# GTR.net
KiCad netlist of a schematic drawn in Altium Designer
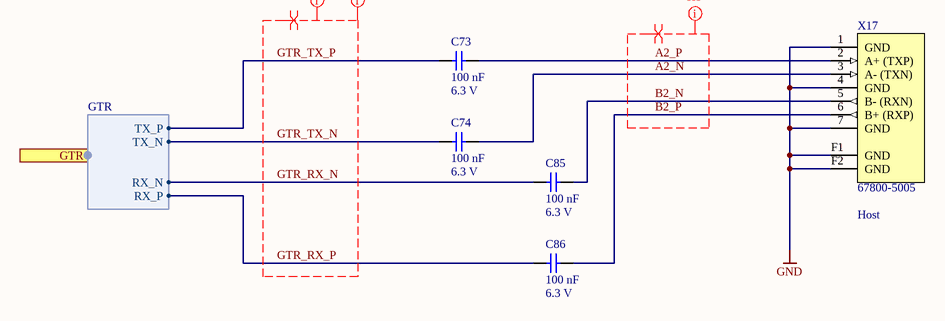
[diagram p0: GTR.schdoc]

(export (version "E")
  (design (tool "Eeschema 10.0.6"))
  (components
    (comp (ref "C73")
      (value "100 nF")
      (footprint "C_0201_TE")
      (description "Generic capacitor")
      (fields
        (field (name "VOLTAGE") "6.3 V")
        (field (name "TOLERANCE") "10 %")
        (field (name "MANUFACTURER PART NUMBER") "UZgen_C_0201_100nF_6.3V_X7R")
        (field (name "CREATED FROM") "MGeier")
      )
      (libsource (lib "user") (part "CAP-NP"))
    )
    (comp (ref "C74")
      (value "100 nF")
      (footprint "C_0201_TE")
      (description "Generic capacitor")
      (fields
        (field (name "VOLTAGE") "6.3 V")
        (field (name "TOLERANCE") "10 %")
        (field (name "MANUFACTURER PART NUMBER") "UZgen_C_0201_100nF_6.3V_X7R")
        (field (name "CREATED FROM") "MGeier")
      )
      (libsource (lib "user") (part "CAP-NP"))
    )
    (comp (ref "C85")
      (value "100 nF")
      (footprint "C_0201_TE")
      (description "Generic capacitor")
      (fields
        (field (name "VOLTAGE") "6.3 V")
        (field (name "TOLERANCE") "10 %")
        (field (name "MANUFACTURER PART NUMBER") "UZgen_C_0201_100nF_6.3V_X7R")
        (field (name "CREATED FROM") "MGeier")
      )
      (libsource (lib "user") (part "CAP-NP"))
    )
    (comp (ref "C86")
      (value "100 nF")
      (footprint "C_0201_TE")
      (description "Generic capacitor")
      (fields
        (field (name "VOLTAGE") "6.3 V")
        (field (name "TOLERANCE") "10 %")
        (field (name "MANUFACTURER PART NUMBER") "UZgen_C_0201_100nF_6.3V_X7R")
        (field (name "CREATED FROM") "MGeier")
      )
      (libsource (lib "user") (part "CAP-NP"))
    )
    (comp (ref "X17")
      (value "67800-5005")
      (footprint "67800-5005")
      (description "SATA Connector - I/O Connectors 7Ckt Vert Signal Hdr SMT w/ locking latch")
      (fields (field (name "MANUFACTURER") "Molex") (field (name "CREATED FROM") "MGremer"))
      (libsource (lib "user") (part "SATA"))
    )
  )
  (nets
    (net (code "2") (name "/A2_N") (class "Default")
      (node (ref "C74") (pin "2") (pinfunction "2_2") (pintype "passive"))
      (node (ref "X17") (pin "3") (pinfunction "A-_(TXN)_3") (pintype "input"))
    )
    (net (code "3") (name "/A2_P") (class "Default")
      (node (ref "C73") (pin "2") (pinfunction "2_2") (pintype "passive"))
      (node (ref "X17") (pin "2") (pinfunction "A+_(TXP)_2") (pintype "input"))
    )
    (net (code "4") (name "/B2_N") (class "Default")
      (node (ref "C85") (pin "2") (pinfunction "2_2") (pintype "passive"))
      (node (ref "X17") (pin "5") (pinfunction "B-_(RXN)_5") (pintype "output"))
    )
    (net (code "5") (name "/B2_P") (class "Default")
      (node (ref "C86") (pin "2") (pinfunction "2_2") (pintype "passive"))
      (node (ref "X17") (pin "6") (pinfunction "B+_(RXP)_6") (pintype "output"))
    )
    (net (code "6") (name "/GTR_RX_N") (class "Default")
      (node (ref "C85") (pin "1") (pinfunction "1_1") (pintype "passive"))
    )
    (net (code "7") (name "/GTR_RX_P") (class "Default")
      (node (ref "C86") (pin "1") (pinfunction "1_1") (pintype "passive"))
    )
    (net (code "8") (name "/GTR_TX_N") (class "Default")
      (node (ref "C74") (pin "1") (pinfunction "1_1") (pintype "passive"))
    )
    (net (code "9") (name "/GTR_TX_P") (class "Default")
      (node (ref "C73") (pin "1") (pinfunction "1_1") (pintype "passive"))
    )
    (net (code "11") (name "GND") (class "Default")
      (node (ref "X17") (pin "1") (pinfunction "GND_1") (pintype "power_in"))
      (node (ref "X17") (pin "4") (pinfunction "GND_4") (pintype "power_in"))
      (node (ref "X17") (pin "7") (pinfunction "GND_7") (pintype "power_in"))
      (node (ref "X17") (pin "F1") (pinfunction "GND_F1") (pintype "power_in"))
      (node (ref "X17") (pin "F2") (pinfunction "GND_F2") (pintype "power_in"))
    )
  )
)
